# prototype_board.net
KiCad netlist of a schematic drawn in EAGLE
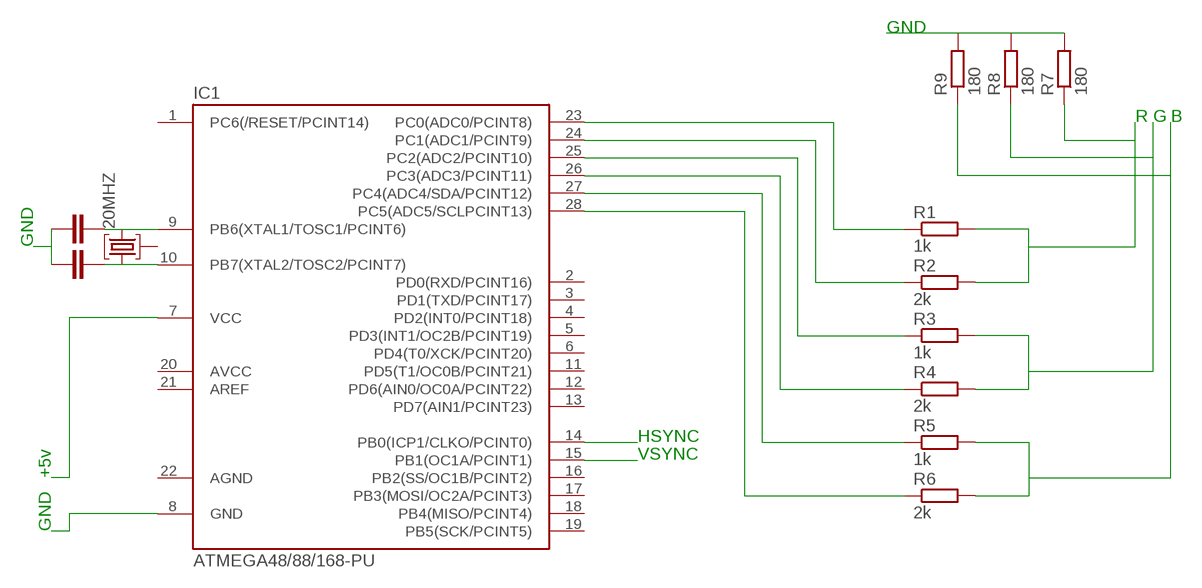
[diagram p0: schematic, sheet 1]

(export (version "E")
  (design (tool "Eeschema 10.0.6"))
  (components
    (comp (ref "20MHZ")
      (value "16M20AUM1")
      (footprint "eagle-import:UM1")
      (libsource (lib "eagle-import") (part "16M20AUM1"))
    )
    (comp (ref "IC1")
      (value "ATMEGA48/88/168-PU")
      (footprint "eagle-import:DIL28-3")
      (libsource (lib "eagle-import") (part "ATMEGA48/88/168-PU"))
    )
    (comp (ref "R1")
      (value "1k")
      (footprint "eagle-import:0309_12")
      (libsource (lib "eagle-import") (part "R-EU_0309/12"))
    )
    (comp (ref "R2")
      (value "2k")
      (footprint "eagle-import:0309_12")
      (libsource (lib "eagle-import") (part "R-EU_0309/12"))
    )
    (comp (ref "R3")
      (value "1k")
      (footprint "eagle-import:0309_12")
      (libsource (lib "eagle-import") (part "R-EU_0309/12"))
    )
    (comp (ref "R4")
      (value "2k")
      (footprint "eagle-import:0309_12")
      (libsource (lib "eagle-import") (part "R-EU_0309/12"))
    )
    (comp (ref "R5")
      (value "1k")
      (footprint "eagle-import:0309_12")
      (libsource (lib "eagle-import") (part "R-EU_0309/12"))
    )
    (comp (ref "R6")
      (value "2k")
      (footprint "eagle-import:0309_12")
      (libsource (lib "eagle-import") (part "R-EU_0309/12"))
    )
    (comp (ref "R7")
      (value "180")
      (footprint "eagle-import:0309_12")
      (libsource (lib "eagle-import") (part "R-EU_0309/12"))
    )
    (comp (ref "R8")
      (value "180")
      (footprint "eagle-import:0309_12")
      (libsource (lib "eagle-import") (part "R-EU_0309/12"))
    )
    (comp (ref "R9")
      (value "180")
      (footprint "eagle-import:0309_12")
      (libsource (lib "eagle-import") (part "R-EU_0309/12"))
    )
  )
  (nets
    (net (code "1") (name "/AGND") (class "Default")
      (node (ref "IC1") (pin "22") (pinfunction "AGND_22") (pintype "power_in"))
    )
    (net (code "2") (name "Net-(IC1-PC0(ADC0{slash}PCINT8))") (class "Default")
      (node (ref "IC1") (pin "23") (pinfunction "PC0(ADC0/PCINT8)_23") (pintype "bidirectional"))
      (node (ref "R1") (pin "1") (pinfunction "1_1") (pintype "passive"))
    )
    (net (code "3") (name "Net-(IC1-PC1(ADC1{slash}PCINT9))") (class "Default")
      (node (ref "IC1") (pin "24") (pinfunction "PC1(ADC1/PCINT9)_24") (pintype "bidirectional"))
      (node (ref "R2") (pin "1") (pinfunction "1_1") (pintype "passive"))
    )
    (net (code "4") (name "Net-(IC1-PC2(ADC2{slash}PCINT10))") (class "Default")
      (node (ref "IC1") (pin "25") (pinfunction "PC2(ADC2/PCINT10)_25") (pintype "bidirectional"))
      (node (ref "R3") (pin "1") (pinfunction "1_1") (pintype "passive"))
    )
    (net (code "5") (name "Net-(IC1-PC3(ADC3{slash}PCINT11))") (class "Default")
      (node (ref "IC1") (pin "26") (pinfunction "PC3(ADC3/PCINT11)_26") (pintype "bidirectional"))
      (node (ref "R4") (pin "1") (pinfunction "1_1") (pintype "passive"))
    )
    (net (code "6") (name "Net-(IC1-PC4(ADC4{slash}SDA{slash}PCINT12))") (class "Default")
      (node (ref "IC1") (pin "27") (pinfunction "PC4(ADC4/SDA/PCINT12)_27") (pintype "bidirectional"))
      (node (ref "R5") (pin "1") (pinfunction "1_1") (pintype "passive"))
    )
    (net (code "7") (name "Net-(IC1-PC5(ADC5{slash}SCLPCINT13))") (class "Default")
      (node (ref "IC1") (pin "28") (pinfunction "PC5(ADC5/SCLPCINT13)_28") (pintype "bidirectional"))
      (node (ref "R6") (pin "1") (pinfunction "1_1") (pintype "passive"))
    )
    (net (code "8") (name "Net-(R1-Pad2)") (class "Default")
      (node (ref "R1") (pin "2") (pinfunction "2_2") (pintype "passive"))
      (node (ref "R2") (pin "2") (pinfunction "2_2") (pintype "passive"))
      (node (ref "R7") (pin "1") (pinfunction "1_1") (pintype "passive"))
    )
    (net (code "9") (name "Net-(R3-Pad2)") (class "Default")
      (node (ref "R3") (pin "2") (pinfunction "2_2") (pintype "passive"))
      (node (ref "R4") (pin "2") (pinfunction "2_2") (pintype "passive"))
      (node (ref "R8") (pin "1") (pinfunction "1_1") (pintype "passive"))
    )
    (net (code "10") (name "Net-(R5-Pad2)") (class "Default")
      (node (ref "R5") (pin "2") (pinfunction "2_2") (pintype "passive"))
      (node (ref "R6") (pin "2") (pinfunction "2_2") (pintype "passive"))
      (node (ref "R9") (pin "1") (pinfunction "1_1") (pintype "passive"))
    )
    (net (code "11") (name "unconnected-(20MHZ-Pad1)") (class "Default")
      (node (ref "20MHZ") (pin "1") (pinfunction "1_1") (pintype "passive"))
    )
    (net (code "12") (name "unconnected-(20MHZ-Pad2)") (class "Default")
      (node (ref "20MHZ") (pin "2") (pinfunction "2_2") (pintype "passive"))
    )
    (net (code "13") (name "unconnected-(20MHZ-Pad3)") (class "Default")
      (node (ref "20MHZ") (pin "3") (pinfunction "3_3") (pintype "passive"))
    )
    (net (code "14") (name "unconnected-(IC1-AREF-Pad21)") (class "Default")
      (node (ref "IC1") (pin "21") (pinfunction "AREF_21") (pintype "passive"))
    )
    (net (code "15") (name "unconnected-(IC1-AVCC-Pad20)") (class "Default")
      (node (ref "IC1") (pin "20") (pinfunction "AVCC_20") (pintype "passive"))
    )
    (net (code "16") (name "unconnected-(IC1-GND-Pad8)") (class "Default")
      (node (ref "IC1") (pin "8") (pinfunction "GND_8") (pintype "power_in"))
    )
    (net (code "17") (name "unconnected-(IC1-PB0(ICP1{slash}CLKO{slash}PCINT0)-Pad14)") (class "Default")
      (node (ref "IC1") (pin "14") (pinfunction "PB0(ICP1/CLKO/PCINT0)_14") (pintype "bidirectional"))
    )
    (net (code "18") (name "unconnected-(IC1-PB1(OC1A{slash}PCINT1)-Pad15)") (class "Default")
      (node (ref "IC1") (pin "15") (pinfunction "PB1(OC1A/PCINT1)_15") (pintype "bidirectional"))
    )
    (net (code "19") (name "unconnected-(IC1-PB2(SS{slash}OC1B{slash}PCINT2)-Pad16)") (class "Default")
      (node (ref "IC1") (pin "16") (pinfunction "PB2(SS/OC1B/PCINT2)_16") (pintype "bidirectional"))
    )
    (net (code "20") (name "unconnected-(IC1-PB3(MOSI{slash}OC2A{slash}PCINT3)-Pad17)") (class "Default")
      (node (ref "IC1") (pin "17") (pinfunction "PB3(MOSI/OC2A/PCINT3)_17") (pintype "bidirectional"))
    )
    (net (code "21") (name "unconnected-(IC1-PB4(MISO{slash}PCINT4)-Pad18)") (class "Default")
      (node (ref "IC1") (pin "18") (pinfunction "PB4(MISO/PCINT4)_18") (pintype "bidirectional"))
    )
    (net (code "22") (name "unconnected-(IC1-PB5(SCK{slash}PCINT5)-Pad19)") (class "Default")
      (node (ref "IC1") (pin "19") (pinfunction "PB5(SCK/PCINT5)_19") (pintype "bidirectional"))
    )
    (net (code "23") (name "unconnected-(IC1-PB6(XTAL1{slash}TOSC1{slash}PCINT6)-Pad9)") (class "Default")
      (node (ref "IC1") (pin "9") (pinfunction "PB6(XTAL1/TOSC1/PCINT6)_9") (pintype "bidirectional"))
    )
    (net (code "24") (name "unconnected-(IC1-PB7(XTAL2{slash}TOSC2{slash}PCINT7)-Pad10)") (class "Default")
      (node (ref "IC1") (pin "10") (pinfunction "PB7(XTAL2/TOSC2/PCINT7)_10") (pintype "bidirectional"))
    )
    (net (code "25") (name "unconnected-(IC1-PC6({slash}RESET{slash}PCINT14)-Pad1)") (class "Default")
      (node (ref "IC1") (pin "1") (pinfunction "PC6(/RESET/PCINT14)_1") (pintype "bidirectional"))
    )
    (net (code "26") (name "unconnected-(IC1-PD0(RXD{slash}PCINT16)-Pad2)") (class "Default")
      (node (ref "IC1") (pin "2") (pinfunction "PD0(RXD/PCINT16)_2") (pintype "bidirectional"))
    )
    (net (code "27") (name "unconnected-(IC1-PD1(TXD{slash}PCINT17)-Pad3)") (class "Default")
      (node (ref "IC1") (pin "3") (pinfunction "PD1(TXD/PCINT17)_3") (pintype "bidirectional"))
    )
    (net (code "28") (name "unconnected-(IC1-PD2(INT0{slash}PCINT18)-Pad4)") (class "Default")
      (node (ref "IC1") (pin "4") (pinfunction "PD2(INT0/PCINT18)_4") (pintype "bidirectional"))
    )
    (net (code "29") (name "unconnected-(IC1-PD3(INT1{slash}OC2B{slash}PCINT19)-Pad5)") (class "Default")
      (node (ref "IC1") (pin "5") (pinfunction "PD3(INT1/OC2B/PCINT19)_5") (pintype "bidirectional"))
    )
    (net (code "30") (name "unconnected-(IC1-PD4(T0{slash}XCK{slash}PCINT20)-Pad6)") (class "Default")
      (node (ref "IC1") (pin "6") (pinfunction "PD4(T0/XCK/PCINT20)_6") (pintype "bidirectional"))
    )
    (net (code "31") (name "unconnected-(IC1-PD5(T1{slash}OC0B{slash}PCINT21)-Pad11)") (class "Default")
      (node (ref "IC1") (pin "11") (pinfunction "PD5(T1/OC0B/PCINT21)_11") (pintype "bidirectional"))
    )
    (net (code "32") (name "unconnected-(IC1-PD6(AIN0{slash}OC0A{slash}PCINT22)-Pad12)") (class "Default")
      (node (ref "IC1") (pin "12") (pinfunction "PD6(AIN0/OC0A/PCINT22)_12") (pintype "bidirectional"))
    )
    (net (code "33") (name "unconnected-(IC1-PD7(AIN1{slash}PCINT23)-Pad13)") (class "Default")
      (node (ref "IC1") (pin "13") (pinfunction "PD7(AIN1/PCINT23)_13") (pintype "bidirectional"))
    )
    (net (code "34") (name "unconnected-(IC1-VCC-Pad7)") (class "Default")
      (node (ref "IC1") (pin "7") (pinfunction "VCC_7") (pintype "power_in"))
    )
    (net (code "35") (name "unconnected-(R7-Pad2)") (class "Default")
      (node (ref "R7") (pin "2") (pinfunction "2_2") (pintype "passive"))
    )
    (net (code "36") (name "unconnected-(R8-Pad2)") (class "Default")
      (node (ref "R8") (pin "2") (pinfunction "2_2") (pintype "passive"))
    )
    (net (code "37") (name "unconnected-(R9-Pad2)") (class "Default")
      (node (ref "R9") (pin "2") (pinfunction "2_2") (pintype "passive"))
    )
  )
)
